# SDC_4.net
KiCad netlist of a schematic drawn in Altium Designer
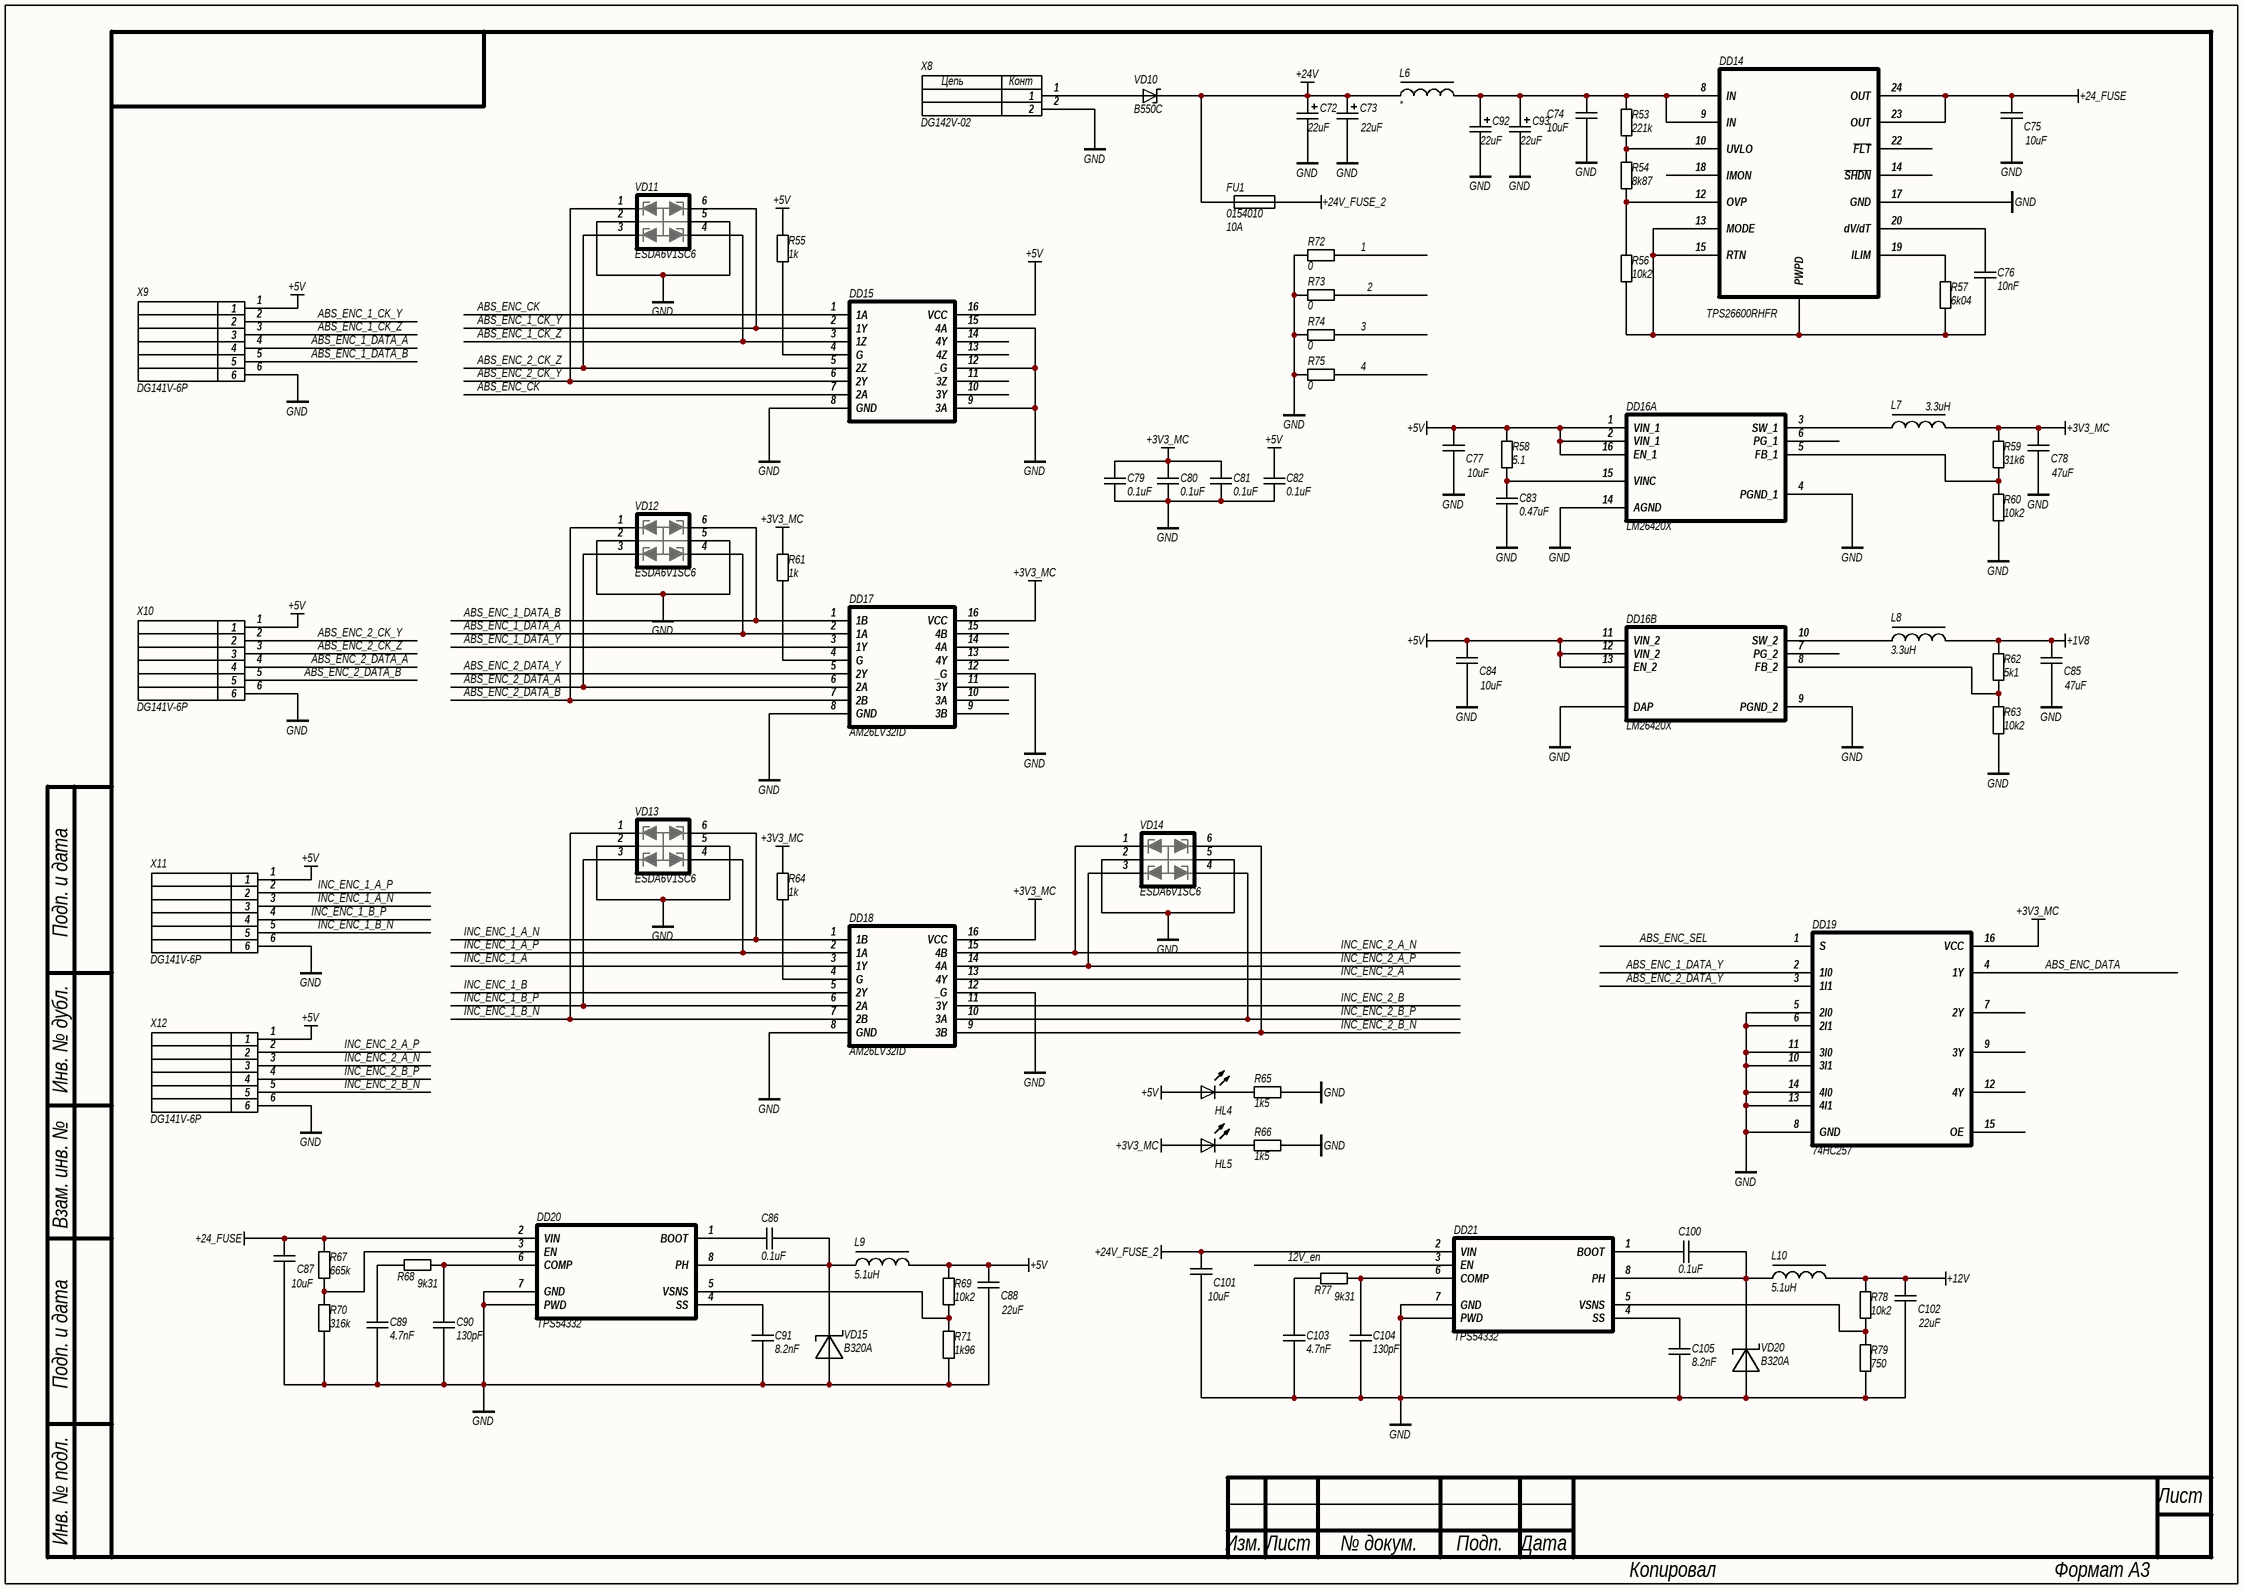
[diagram p0: SDC_4.SchDoc]

(export (version "E")
  (design (tool "Eeschema 10.0.6"))
  (components
    (comp (ref "C72")
      (value "22uF")
      (footprint "Cap_D")
      (description "Polarized Capacitor (Surface Mount)")
      (fields (field (name "VOLTAGE") "35V") (field (name "Comment") "caseD"))
      (libsource (lib "VKA") (part "Cap Pol_D"))
    )
    (comp (ref "C73")
      (value "22uF")
      (footprint "Cap_D")
      (description "Polarized Capacitor (Surface Mount)")
      (fields (field (name "VOLTAGE") "35V") (field (name "Comment") "caseD"))
      (libsource (lib "VKA") (part "Cap Pol_D"))
    )
    (comp (ref "C74")
      (value "10uF")
      (footprint "C1210")
      (description "SMD Capacitor")
      (fields (field (name "MANUFACTURER") "Murata") (field (name "TOLERANCE") "10%"))
      (libsource (lib "VKA") (part "CAP"))
    )
    (comp (ref "C75")
      (value "10uF")
      (footprint "C1210")
      (description "SMD Capacitor")
      (fields (field (name "MANUFACTURER") "Murata") (field (name "TOLERANCE") "10%"))
      (libsource (lib "VKA") (part "CAP"))
    )
    (comp (ref "C76")
      (value "10nF")
      (footprint "C0603")
      (description "SMD Capacitor")
      (fields (field (name "MANUFACTURER") "Murata") (field (name "TOLERANCE") "10%"))
      (libsource (lib "VKA") (part "CAP"))
    )
    (comp (ref "C77")
      (value "10uF")
      (footprint "C1210")
      (description "SMD Capacitor")
      (fields (field (name "MANUFACTURER") "Murata") (field (name "TOLERANCE") "10%"))
      (libsource (lib "VKA") (part "CAP"))
    )
    (comp (ref "C78")
      (value "47uF")
      (footprint "C1210")
      (description "SMD Capacitor")
      (fields (field (name "MANUFACTURER") "Murata") (field (name "TOLERANCE") "10%"))
      (libsource (lib "VKA") (part "CAP"))
    )
    (comp (ref "C79")
      (value "0.1uF")
      (footprint "C0603")
      (description "SMD Capacitor")
      (fields (field (name "MANUFACTURER") "Murata") (field (name "TOLERANCE") "10%"))
      (libsource (lib "VKA") (part "CAP"))
    )
    (comp (ref "C80")
      (value "0.1uF")
      (footprint "C0603")
      (description "SMD Capacitor")
      (fields (field (name "MANUFACTURER") "Murata") (field (name "TOLERANCE") "10%"))
      (libsource (lib "VKA") (part "CAP"))
    )
    (comp (ref "C81")
      (value "0.1uF")
      (footprint "C0603")
      (description "SMD Capacitor")
      (fields (field (name "MANUFACTURER") "Murata") (field (name "TOLERANCE") "10%"))
      (libsource (lib "VKA") (part "CAP"))
    )
    (comp (ref "C82")
      (value "0.1uF")
      (footprint "C0603")
      (description "SMD Capacitor")
      (fields (field (name "MANUFACTURER") "Murata") (field (name "TOLERANCE") "10%"))
      (libsource (lib "VKA") (part "CAP"))
    )
    (comp (ref "C83")
      (value "0.47uF")
      (footprint "C0603")
      (description "SMD Capacitor")
      (fields (field (name "MANUFACTURER") "Murata") (field (name "TOLERANCE") "10%"))
      (libsource (lib "VKA") (part "CAP"))
    )
    (comp (ref "C84")
      (value "10uF")
      (footprint "C1210")
      (description "SMD Capacitor")
      (fields (field (name "MANUFACTURER") "Murata") (field (name "TOLERANCE") "10%"))
      (libsource (lib "VKA") (part "CAP"))
    )
    (comp (ref "C85")
      (value "47uF")
      (footprint "C1210")
      (description "SMD Capacitor")
      (fields (field (name "MANUFACTURER") "Murata") (field (name "TOLERANCE") "10%"))
      (libsource (lib "VKA") (part "CAP"))
    )
    (comp (ref "C86")
      (value "0.1uF")
      (footprint "C0603")
      (description "SMD Capacitor")
      (fields (field (name "MANUFACTURER") "Murata") (field (name "TOLERANCE") "10%"))
      (libsource (lib "VKA") (part "CAP"))
    )
    (comp (ref "C87")
      (value "10uF")
      (footprint "C0805")
      (description "SMD Capacitor")
      (fields (field (name "MANUFACTURER") "Murata") (field (name "TOLERANCE") "10%"))
      (libsource (lib "VKA") (part "CAP"))
    )
    (comp (ref "C88")
      (value "22uF")
      (footprint "C1210")
      (description "SMD Capacitor")
      (fields (field (name "MANUFACTURER") "Murata") (field (name "TOLERANCE") "10%"))
      (libsource (lib "VKA") (part "CAP"))
    )
    (comp (ref "C89")
      (value "4.7nF")
      (footprint "C0603")
      (description "SMD Capacitor")
      (fields (field (name "MANUFACTURER") "Murata") (field (name "TOLERANCE") "10%"))
      (libsource (lib "VKA") (part "CAP"))
    )
    (comp (ref "C90")
      (value "130pF")
      (footprint "C0603")
      (description "SMD Capacitor")
      (fields (field (name "MANUFACTURER") "Murata") (field (name "TOLERANCE") "10%"))
      (libsource (lib "VKA") (part "CAP"))
    )
    (comp (ref "C91")
      (value "8.2nF")
      (footprint "C0603")
      (description "SMD Capacitor")
      (fields (field (name "MANUFACTURER") "Murata") (field (name "TOLERANCE") "10%"))
      (libsource (lib "VKA") (part "CAP"))
    )
    (comp (ref "C92")
      (value "22uF")
      (footprint "Cap_D")
      (description "Polarized Capacitor (Surface Mount)")
      (fields (field (name "VOLTAGE") "35V") (field (name "Comment") "caseD"))
      (libsource (lib "VKA") (part "Cap Pol_D"))
    )
    (comp (ref "C93")
      (value "22uF")
      (footprint "Cap_D")
      (description "Polarized Capacitor (Surface Mount)")
      (fields (field (name "VOLTAGE") "35V") (field (name "Comment") "caseD"))
      (libsource (lib "VKA") (part "Cap Pol_D"))
    )
    (comp (ref "C100")
      (value "0.1uF")
      (footprint "C0603")
      (description "SMD Capacitor")
      (fields (field (name "MANUFACTURER") "Murata") (field (name "TOLERANCE") "10%"))
      (libsource (lib "VKA") (part "CAP"))
    )
    (comp (ref "C101")
      (value "10uF")
      (footprint "C0805")
      (description "SMD Capacitor")
      (fields (field (name "MANUFACTURER") "Murata") (field (name "TOLERANCE") "10%"))
      (libsource (lib "VKA") (part "CAP"))
    )
    (comp (ref "C102")
      (value "22uF")
      (footprint "C1210")
      (description "SMD Capacitor")
      (fields (field (name "MANUFACTURER") "Murata") (field (name "TOLERANCE") "10%"))
      (libsource (lib "VKA") (part "CAP"))
    )
    (comp (ref "C103")
      (value "4.7nF")
      (footprint "C0603")
      (description "SMD Capacitor")
      (fields (field (name "MANUFACTURER") "Murata") (field (name "TOLERANCE") "10%"))
      (libsource (lib "VKA") (part "CAP"))
    )
    (comp (ref "C104")
      (value "130pF")
      (footprint "C0603")
      (description "SMD Capacitor")
      (fields (field (name "MANUFACTURER") "Murata") (field (name "TOLERANCE") "10%"))
      (libsource (lib "VKA") (part "CAP"))
    )
    (comp (ref "C105")
      (value "8.2nF")
      (footprint "C0603")
      (description "SMD Capacitor")
      (fields (field (name "MANUFACTURER") "Murata") (field (name "TOLERANCE") "10%"))
      (libsource (lib "VKA") (part "CAP"))
    )
    (comp (ref "DD14")
      (value "TPS26600RHFR")
      (footprint "VQFN24")
      (description "Industrial eFuse")
      (fields (field (name "VOLTAGE") "60V"))
      (libsource (lib "VKA") (part "TPS26600RHFR"))
    )
    (comp (ref "DD15")
      (value "AM26C31CD")
      (footprint "SO-16_N")
      (description "RS-422 transmitter")
      (libsource (lib "VKA") (part "AM26C31CD"))
    )
    (comp (ref "DD16") (value "LM26420X") (footprint "WQFN16") (libsource (lib "VKA") (part "LM26420X")))
    (comp (ref "DD17")
      (value "AM26LV32ID")
      (footprint "SO-16_N")
      (description "RS-422 receiver")
      (libsource (lib "VKA") (part "AM26LV32ID"))
    )
    (comp (ref "DD18")
      (value "AM26LV32ID")
      (footprint "SO-16_N")
      (description "RS-422 receiver")
      (libsource (lib "VKA") (part "AM26LV32ID"))
    )
    (comp (ref "DD19")
      (value "74HC257")
      (footprint "SO-16_N")
      (description "MUX")
      (libsource (lib "VKA") (part "74HC257"))
    )
    (comp (ref "DD20") (value "TPS54332") (footprint "DDA") (libsource (lib "VKA") (part "TPS54332")))
    (comp (ref "DD21") (value "TPS54332") (footprint "DDA") (libsource (lib "VKA") (part "TPS54332")))
    (comp (ref "FU1")
      (value "0154010")
      (footprint "omni_block_154")
      (description "omni fuse block")
      (fields (field (name "CURRENT") "10A"))
      (libsource (lib "DSP") (part "0154010"))
    )
    (comp (ref "HL4") (value "LED0603") (footprint "LED0603") (libsource (lib "VKA") (part "LED0603")))
    (comp (ref "HL5") (value "LED0603") (footprint "LED0603") (libsource (lib "VKA") (part "LED0603")))
    (comp (ref "L6")
      (value "XAL6060")
      (footprint "XAL6060")
      (description "chip inductor")
      (fields (field (name "ALTIUM_VALUE") "*"))
      (libsource (lib "VKA") (part "XAL6060"))
    )
    (comp (ref "L7")
      (value "3.3uH")
      (footprint "XAL4030")
      (description "chip inductor")
      (fields (field (name "Comment") "XAL4030"))
      (libsource (lib "VKA") (part "XAL4030"))
    )
    (comp (ref "L8")
      (value "3.3uH")
      (footprint "XAL4030")
      (description "chip inductor")
      (fields (field (name "Comment") "XAL4030"))
      (libsource (lib "VKA") (part "XAL4030"))
    )
    (comp (ref "L9")
      (value "5.1uH")
      (footprint "XAL5050")
      (description "chip inductor")
      (fields (field (name "Comment") "XAL5050"))
      (libsource (lib "VKA") (part "XAL5050"))
    )
    (comp (ref "L10")
      (value "5.1uH")
      (footprint "XAL5050")
      (description "chip inductor")
      (fields (field (name "Comment") "XAL5050"))
      (libsource (lib "VKA") (part "XAL5050"))
    )
    (comp (ref "R53")
      (value "221k")
      (footprint "R0603")
      (description "SMD Resistor")
      (fields (field (name "POWER") "0.062 Wt") (field (name "TOLERANCE") "5%"))
      (libsource (lib "VKA") (part "RES"))
    )
    (comp (ref "R54")
      (value "8k87")
      (footprint "R0603")
      (description "SMD Resistor")
      (fields (field (name "POWER") "0.062 Wt") (field (name "TOLERANCE") "5%"))
      (libsource (lib "VKA") (part "RES"))
    )
    (comp (ref "R55")
      (value "1k")
      (footprint "R0603")
      (description "SMD Resistor")
      (fields (field (name "POWER") "0.062 Wt") (field (name "TOLERANCE") "5%"))
      (libsource (lib "VKA") (part "RES"))
    )
    (comp (ref "R56")
      (value "10k2")
      (footprint "R0603")
      (description "SMD Resistor")
      (fields (field (name "POWER") "0.062 Wt") (field (name "TOLERANCE") "5%"))
      (libsource (lib "VKA") (part "RES"))
    )
    (comp (ref "R57")
      (value "6k04")
      (footprint "R0603")
      (description "SMD Resistor")
      (fields (field (name "POWER") "0.062 Wt") (field (name "TOLERANCE") "5%"))
      (libsource (lib "VKA") (part "RES"))
    )
    (comp (ref "R58")
      (value "5.1")
      (footprint "R0603")
      (description "SMD Resistor")
      (fields (field (name "POWER") "0.062 Wt") (field (name "TOLERANCE") "5%"))
      (libsource (lib "VKA") (part "RES"))
    )
    (comp (ref "R59")
      (value "31k6")
      (footprint "R0603")
      (description "SMD Resistor")
      (fields (field (name "POWER") "0.062 Wt") (field (name "TOLERANCE") "5%"))
      (libsource (lib "VKA") (part "RES"))
    )
    (comp (ref "R60")
      (value "10k2")
      (footprint "R0603")
      (description "SMD Resistor")
      (fields (field (name "POWER") "0.062 Wt") (field (name "TOLERANCE") "5%"))
      (libsource (lib "VKA") (part "RES"))
    )
    (comp (ref "R61")
      (value "1k")
      (footprint "R0603")
      (description "SMD Resistor")
      (fields (field (name "POWER") "0.062 Wt") (field (name "TOLERANCE") "5%"))
      (libsource (lib "VKA") (part "RES"))
    )
    (comp (ref "R62")
      (value "5k1")
      (footprint "R0603")
      (description "SMD Resistor")
      (fields (field (name "POWER") "0.062 Wt") (field (name "TOLERANCE") "5%"))
      (libsource (lib "VKA") (part "RES"))
    )
    (comp (ref "R63")
      (value "10k2")
      (footprint "R0603")
      (description "SMD Resistor")
      (fields (field (name "POWER") "0.062 Wt") (field (name "TOLERANCE") "5%"))
      (libsource (lib "VKA") (part "RES"))
    )
    (comp (ref "R64")
      (value "1k")
      (footprint "R0603")
      (description "SMD Resistor")
      (fields (field (name "POWER") "0.062 Wt") (field (name "TOLERANCE") "5%"))
      (libsource (lib "VKA") (part "RES"))
    )
    (comp (ref "R65")
      (value "1k5")
      (footprint "R0603")
      (description "SMD Resistor")
      (fields (field (name "POWER") "0.062 Wt") (field (name "TOLERANCE") "5%"))
      (libsource (lib "") (part "RES_1"))
    )
    (comp (ref "R66")
      (value "1k5")
      (footprint "R0603")
      (description "SMD Resistor")
      (fields (field (name "POWER") "0.062 Wt") (field (name "TOLERANCE") "5%"))
      (libsource (lib "") (part "RES_1"))
    )
    (comp (ref "R67")
      (value "665k")
      (footprint "R0603")
      (description "SMD Resistor")
      (fields (field (name "POWER") "0.062 Wt") (field (name "TOLERANCE") "5%"))
      (libsource (lib "VKA") (part "RES"))
    )
    (comp (ref "R68")
      (value "9k31")
      (footprint "R0603")
      (description "SMD Resistor")
      (fields (field (name "POWER") "0.062 Wt") (field (name "TOLERANCE") "5%"))
      (libsource (lib "") (part "RES_1"))
    )
    (comp (ref "R69")
      (value "10k2")
      (footprint "R0603")
      (description "SMD Resistor")
      (fields (field (name "POWER") "0.062 Wt") (field (name "TOLERANCE") "5%"))
      (libsource (lib "VKA") (part "RES"))
    )
    (comp (ref "R70")
      (value "316k")
      (footprint "R0603")
      (description "SMD Resistor")
      (fields (field (name "POWER") "0.062 Wt") (field (name "TOLERANCE") "5%"))
      (libsource (lib "VKA") (part "RES"))
    )
    (comp (ref "R71")
      (value "1k96")
      (footprint "R0603")
      (description "SMD Resistor")
      (fields (field (name "POWER") "0.062 Wt") (field (name "TOLERANCE") "5%"))
      (libsource (lib "VKA") (part "RES"))
    )
    (comp (ref "R72")
      (value "0")
      (footprint "R0603")
      (description "SMD Resistor")
      (fields (field (name "POWER") "0.062 Wt") (field (name "TOLERANCE") "5%"))
      (libsource (lib "") (part "RES_1"))
    )
    (comp (ref "R73")
      (value "0")
      (footprint "R0603")
      (description "SMD Resistor")
      (fields (field (name "POWER") "0.062 Wt") (field (name "TOLERANCE") "5%"))
      (libsource (lib "") (part "RES_1"))
    )
    (comp (ref "R74")
      (value "0")
      (footprint "R0603")
      (description "SMD Resistor")
      (fields (field (name "POWER") "0.062 Wt") (field (name "TOLERANCE") "5%"))
      (libsource (lib "") (part "RES_1"))
    )
    (comp (ref "R75")
      (value "0")
      (footprint "R0603")
      (description "SMD Resistor")
      (fields (field (name "POWER") "0.062 Wt") (field (name "TOLERANCE") "5%"))
      (libsource (lib "") (part "RES_1"))
    )
    (comp (ref "R77")
      (value "9k31")
      (footprint "R0603")
      (description "SMD Resistor")
      (fields (field (name "POWER") "0.062 Wt") (field (name "TOLERANCE") "5%"))
      (libsource (lib "") (part "RES_1"))
    )
    (comp (ref "R78")
      (value "10k2")
      (footprint "R0603")
      (description "SMD Resistor")
      (fields (field (name "POWER") "0.062 Wt") (field (name "TOLERANCE") "5%"))
      (libsource (lib "VKA") (part "RES"))
    )
    (comp (ref "R79")
      (value "750")
      (footprint "R0603")
      (description "SMD Resistor")
      (fields (field (name "POWER") "0.062 Wt") (field (name "TOLERANCE") "5%"))
      (libsource (lib "VKA") (part "RES"))
    )
    (comp (ref "VD10")
      (value "B550C")
      (footprint "SMC-DO214")
      (description "DIODE, SCHOTTKY, 5A, 50V, SMC")
      (libsource (lib "VKA") (part "B550C"))
    )
    (comp (ref "VD11")
      (value "ESDA6V1SC6")
      (footprint "SOT23-6")
      (description "4-line ESD protection")
      (libsource (lib "VKA") (part "ESDA6V1SC6"))
    )
    (comp (ref "VD12")
      (value "ESDA6V1SC6")
      (footprint "SOT23-6")
      (description "4-line ESD protection")
      (libsource (lib "VKA") (part "ESDA6V1SC6"))
    )
    (comp (ref "VD13")
      (value "ESDA6V1SC6")
      (footprint "SOT23-6")
      (description "4-line ESD protection")
      (libsource (lib "VKA") (part "ESDA6V1SC6"))
    )
    (comp (ref "VD14")
      (value "ESDA6V1SC6")
      (footprint "SOT23-6")
      (description "4-line ESD protection")
      (libsource (lib "VKA") (part "ESDA6V1SC6"))
    )
    (comp (ref "VD15")
      (value "B320A")
      (footprint "SMA-DO214")
      (description "Shottky diode")
      (libsource (lib "VKA") (part "B320A"))
    )
    (comp (ref "VD20")
      (value "B320A")
      (footprint "SMA-DO214")
      (description "Shottky diode")
      (libsource (lib "VKA") (part "B320A"))
    )
    (comp (ref "X8") (value "DG142V-02") (footprint "DG142V-02") (libsource (lib "VKA") (part "DG142V-02")))
    (comp (ref "X9")
      (value "DG141V-6P")
      (footprint "DG141V-06P")
      (description "wire connector")
      (libsource (lib "VKA") (part "DG141V-6P"))
    )
    (comp (ref "X10")
      (value "DG141V-6P")
      (footprint "DG141V-06P")
      (description "wire connector")
      (libsource (lib "VKA") (part "DG141V-6P"))
    )
    (comp (ref "X11")
      (value "DG141V-6P")
      (footprint "DG141V-06P")
      (description "wire connector")
      (libsource (lib "VKA") (part "DG141V-6P"))
    )
    (comp (ref "X12")
      (value "DG141V-6P")
      (footprint "DG141V-06P")
      (description "wire connector")
      (libsource (lib "VKA") (part "DG141V-6P"))
    )
  )
  (nets
    (net (code "1") (name "+1V8") (class "Default")
      (node (ref "C85") (pin "2") (pinfunction "2_2") (pintype "passive"))
      (node (ref "L8") (pin "2") (pinfunction "2_2") (pintype "passive"))
      (node (ref "R62") (pin "2") (pinfunction "2_2") (pintype "passive"))
    )
    (net (code "2") (name "+3V3_MC") (class "Default")
      (node (ref "C78") (pin "2") (pinfunction "2_2") (pintype "passive"))
      (node (ref "C79") (pin "2") (pinfunction "2_2") (pintype "passive"))
      (node (ref "C80") (pin "2") (pinfunction "2_2") (pintype "passive"))
      (node (ref "C81") (pin "2") (pinfunction "2_2") (pintype "passive"))
      (node (ref "DD17") (pin "16") (pinfunction "VCC_16") (pintype "passive"))
      (node (ref "DD18") (pin "16") (pinfunction "VCC_16") (pintype "passive"))
      (node (ref "DD19") (pin "16") (pinfunction "VCC_16") (pintype "passive"))
      (node (ref "HL5") (pin "1") (pinfunction "A_1") (pintype "passive"))
      (node (ref "L7") (pin "2") (pinfunction "2_2") (pintype "passive"))
      (node (ref "R59") (pin "2") (pinfunction "2_2") (pintype "passive"))
      (node (ref "R61") (pin "2") (pinfunction "2_2") (pintype "passive"))
      (node (ref "R64") (pin "2") (pinfunction "2_2") (pintype "passive"))
    )
    (net (code "3") (name "+5V") (class "Default")
      (node (ref "C77") (pin "2") (pinfunction "2_2") (pintype "passive"))
      (node (ref "C82") (pin "2") (pinfunction "2_2") (pintype "passive"))
      (node (ref "C84") (pin "2") (pinfunction "2_2") (pintype "passive"))
      (node (ref "C88") (pin "2") (pinfunction "2_2") (pintype "passive"))
      (node (ref "DD15") (pin "16") (pinfunction "VCC_16") (pintype "passive"))
      (node (ref "DD16") (pin "1") (pinfunction "VIN_1_1") (pintype "passive"))
      (node (ref "DD16") (pin "11") (pinfunction "VIN_2_11") (pintype "passive"))
      (node (ref "DD16") (pin "12") (pinfunction "VIN_2_12") (pintype "passive"))
      (node (ref "DD16") (pin "13") (pinfunction "EN_2_13") (pintype "passive"))
      (node (ref "DD16") (pin "16") (pinfunction "EN_1_16") (pintype "passive"))
      (node (ref "DD16") (pin "2") (pinfunction "VIN_1_2") (pintype "passive"))
      (node (ref "HL4") (pin "1") (pinfunction "A_1") (pintype "passive"))
      (node (ref "L9") (pin "2") (pinfunction "2_2") (pintype "passive"))
      (node (ref "R55") (pin "2") (pinfunction "2_2") (pintype "passive"))
      (node (ref "R58") (pin "2") (pinfunction "2_2") (pintype "passive"))
      (node (ref "R69") (pin "2") (pinfunction "2_2") (pintype "passive"))
      (node (ref "X10") (pin "1") (pinfunction "1_1") (pintype "passive"))
      (node (ref "X11") (pin "1") (pinfunction "1_1") (pintype "passive"))
      (node (ref "X12") (pin "1") (pinfunction "1_1") (pintype "passive"))
      (node (ref "X9") (pin "1") (pinfunction "1_1") (pintype "passive"))
    )
    (net (code "4") (name "+12V") (class "Default")
      (node (ref "C102") (pin "2") (pinfunction "2_2") (pintype "passive"))
      (node (ref "L10") (pin "2") (pinfunction "2_2") (pintype "passive"))
      (node (ref "R78") (pin "2") (pinfunction "2_2") (pintype "passive"))
    )
    (net (code "5") (name "+24V") (class "Default")
      (node (ref "C72") (pin "1") (pinfunction "1_1") (pintype "passive"))
      (node (ref "C73") (pin "1") (pinfunction "1_1") (pintype "passive"))
      (node (ref "FU1") (pin "1") (pinfunction "1_1") (pintype "passive"))
      (node (ref "L6") (pin "1") (pinfunction "1_1") (pintype "passive"))
      (node (ref "VD10") (pin "2") (pinfunction "K_2") (pintype "passive"))
    )
    (net (code "6") (name "+24V_FUSE_2") (class "Default")
      (node (ref "C101") (pin "2") (pinfunction "2_2") (pintype "passive"))
      (node (ref "DD21") (pin "2") (pinfunction "VIN_2") (pintype "passive"))
      (node (ref "FU1") (pin "2") (pinfunction "2_2") (pintype "passive"))
    )
    (net (code "7") (name "+24_FUSE") (class "Default")
      (node (ref "C75") (pin "2") (pinfunction "2_2") (pintype "passive"))
      (node (ref "C87") (pin "2") (pinfunction "2_2") (pintype "passive"))
      (node (ref "DD14") (pin "23") (pinfunction "OUT_23") (pintype "passive"))
      (node (ref "DD14") (pin "24") (pinfunction "OUT_24") (pintype "passive"))
      (node (ref "DD20") (pin "2") (pinfunction "VIN_2") (pintype "passive"))
      (node (ref "R67") (pin "2") (pinfunction "2_2") (pintype "passive"))
    )
    (net (code "8") (name "/1") (class "Default")
      (node (ref "R72") (pin "1") (pinfunction "1_1") (pintype "passive"))
    )
    (net (code "9") (name "/2") (class "Default")
      (node (ref "R73") (pin "1") (pinfunction "1_1") (pintype "passive"))
    )
    (net (code "10") (name "/3") (class "Default")
      (node (ref "R74") (pin "1") (pinfunction "1_1") (pintype "passive"))
    )
    (net (code "11") (name "/4") (class "Default")
      (node (ref "R75") (pin "1") (pinfunction "1_1") (pintype "passive"))
    )
    (net (code "12") (name "/12V_en") (class "Default")
      (node (ref "DD21") (pin "3") (pinfunction "EN_3") (pintype "passive"))
    )
    (net (code "13") (name "/ABS_ENC_1_CK_Y") (class "Default")
      (node (ref "DD15") (pin "2") (pinfunction "1Y_2") (pintype "passive"))
      (node (ref "VD11") (pin "6") (pinfunction "6_6") (pintype "passive"))
      (node (ref "X9") (pin "2") (pinfunction "2_2") (pintype "passive"))
    )
    (net (code "14") (name "/ABS_ENC_1_CK_Z") (class "Default")
      (node (ref "DD15") (pin "3") (pinfunction "1Z_3") (pintype "passive"))
      (node (ref "VD11") (pin "4") (pinfunction "4_4") (pintype "passive"))
      (node (ref "X9") (pin "3") (pinfunction "3_3") (pintype "passive"))
    )
    (net (code "15") (name "/ABS_ENC_1_DATA_A") (class "Default")
      (node (ref "DD17") (pin "2") (pinfunction "1A_2") (pintype "passive"))
      (node (ref "VD12") (pin "4") (pinfunction "4_4") (pintype "passive"))
      (node (ref "X9") (pin "4") (pinfunction "4_4") (pintype "passive"))
    )
    (net (code "16") (name "/ABS_ENC_1_DATA_B") (class "Default")
      (node (ref "DD17") (pin "1") (pinfunction "1B_1") (pintype "passive"))
      (node (ref "VD12") (pin "6") (pinfunction "6_6") (pintype "passive"))
      (node (ref "X9") (pin "5") (pinfunction "5_5") (pintype "passive"))
    )
    (net (code "17") (name "/ABS_ENC_1_DATA_Y") (class "Default")
      (node (ref "DD17") (pin "3") (pinfunction "1Y_3") (pintype "passive"))
      (node (ref "DD19") (pin "2") (pinfunction "1I0_2") (pintype "passive"))
    )
    (net (code "18") (name "/ABS_ENC_2_CK_Y") (class "Default")
      (node (ref "DD15") (pin "6") (pinfunction "2Y_6") (pintype "passive"))
      (node (ref "VD11") (pin "1") (pinfunction "1_1") (pintype "passive"))
      (node (ref "X10") (pin "2") (pinfunction "2_2") (pintype "passive"))
    )
    (net (code "19") (name "/ABS_ENC_2_CK_Z") (class "Default")
      (node (ref "DD15") (pin "5") (pinfunction "2Z_5") (pintype "passive"))
      (node (ref "VD11") (pin "3") (pinfunction "3_3") (pintype "passive"))
      (node (ref "X10") (pin "3") (pinfunction "3_3") (pintype "passive"))
    )
    (net (code "20") (name "/ABS_ENC_2_DATA_A") (class "Default")
      (node (ref "DD17") (pin "6") (pinfunction "2A_6") (pintype "passive"))
      (node (ref "VD12") (pin "3") (pinfunction "3_3") (pintype "passive"))
      (node (ref "X10") (pin "4") (pinfunction "4_4") (pintype "passive"))
    )
    (net (code "21") (name "/ABS_ENC_2_DATA_B") (class "Default")
      (node (ref "DD17") (pin "7") (pinfunction "2B_7") (pintype "passive"))
      (node (ref "VD12") (pin "1") (pinfunction "1_1") (pintype "passive"))
      (node (ref "X10") (pin "5") (pinfunction "5_5") (pintype "passive"))
    )
    (net (code "22") (name "/ABS_ENC_2_DATA_Y") (class "Default")
      (node (ref "DD17") (pin "5") (pinfunction "2Y_5") (pintype "passive"))
      (node (ref "DD19") (pin "3") (pinfunction "1I1_3") (pintype "passive"))
    )
    (net (code "23") (name "/ABS_ENC_CK") (class "Default")
      (node (ref "DD15") (pin "1") (pinfunction "1A_1") (pintype "passive"))
      (node (ref "DD15") (pin "7") (pinfunction "2A_7") (pintype "passive"))
    )
    (net (code "24") (name "/ABS_ENC_DATA") (class "Default")
      (node (ref "DD19") (pin "4") (pinfunction "1Y_4") (pintype "passive"))
    )
    (net (code "25") (name "/ABS_ENC_SEL") (class "Default")
      (node (ref "DD19") (pin "1") (pinfunction "S_1") (pintype "passive"))
    )
    (net (code "26") (name "/INC_ENC_1_A") (class "Default")
      (node (ref "DD18") (pin "3") (pinfunction "1Y_3") (pintype "passive"))
    )
    (net (code "27") (name "/INC_ENC_1_A_N") (class "Default")
      (node (ref "DD18") (pin "1") (pinfunction "1B_1") (pintype "passive"))
      (node (ref "VD13") (pin "6") (pinfunction "6_6") (pintype "passive"))
      (node (ref "X11") (pin "3") (pinfunction "3_3") (pintype "passive"))
    )
    (net (code "28") (name "/INC_ENC_1_A_P") (class "Default")
      (node (ref "DD18") (pin "2") (pinfunction "1A_2") (pintype "passive"))
      (node (ref "VD13") (pin "4") (pinfunction "4_4") (pintype "passive"))
      (node (ref "X11") (pin "2") (pinfunction "2_2") (pintype "passive"))
    )
    (net (code "29") (name "/INC_ENC_1_B") (class "Default")
      (node (ref "DD18") (pin "5") (pinfunction "2Y_5") (pintype "passive"))
    )
    (net (code "30") (name "/INC_ENC_1_B_N") (class "Default")
      (node (ref "DD18") (pin "7") (pinfunction "2B_7") (pintype "passive"))
      (node (ref "VD13") (pin "1") (pinfunction "1_1") (pintype "passive"))
      (node (ref "X11") (pin "5") (pinfunction "5_5") (pintype "passive"))
    )
    (net (code "31") (name "/INC_ENC_1_B_P") (class "Default")
      (node (ref "DD18") (pin "6") (pinfunction "2A_6") (pintype "passive"))
      (node (ref "VD13") (pin "3") (pinfunction "3_3") (pintype "passive"))
      (node (ref "X11") (pin "4") (pinfunction "4_4") (pintype "passive"))
    )
    (net (code "32") (name "/INC_ENC_2_A") (class "Default")
      (node (ref "DD18") (pin "13") (pinfunction "4Y_13") (pintype "passive"))
    )
    (net (code "33") (name "/INC_ENC_2_A_N") (class "Default")
      (node (ref "DD18") (pin "15") (pinfunction "4B_15") (pintype "passive"))
      (node (ref "VD14") (pin "1") (pinfunction "1_1") (pintype "passive"))
      (node (ref "X12") (pin "3") (pinfunction "3_3") (pintype "passive"))
    )
    (net (code "34") (name "/INC_ENC_2_A_P") (class "Default")
      (node (ref "DD18") (pin "14") (pinfunction "4A_14") (pintype "passive"))
      (node (ref "VD14") (pin "3") (pinfunction "3_3") (pintype "passive"))
      (node (ref "X12") (pin "2") (pinfunction "2_2") (pintype "passive"))
    )
    (net (code "35") (name "/INC_ENC_2_B") (class "Default")
      (node (ref "DD18") (pin "11") (pinfunction "3Y_11") (pintype "passive"))
    )
    (net (code "36") (name "/INC_ENC_2_B_N") (class "Default")
      (node (ref "DD18") (pin "9") (pinfunction "3B_9") (pintype "passive"))
      (node (ref "VD14") (pin "6") (pinfunction "6_6") (pintype "passive"))
      (node (ref "X12") (pin "5") (pinfunction "5_5") (pintype "passive"))
    )
    (net (code "37") (name "/INC_ENC_2_B_P") (class "Default")
      (node (ref "DD18") (pin "10") (pinfunction "3A_10") (pintype "passive"))
      (node (ref "VD14") (pin "4") (pinfunction "4_4") (pintype "passive"))
      (node (ref "X12") (pin "4") (pinfunction "4_4") (pintype "passive"))
    )
    (net (code "38") (name "GND") (class "Default")
      (node (ref "C101") (pin "1") (pinfunction "1_1") (pintype "passive"))
      (node (ref "C102") (pin "1") (pinfunction "1_1") (pintype "passive"))
      (node (ref "C103") (pin "1") (pinfunction "1_1") (pintype "passive"))
      (node (ref "C104") (pin "1") (pinfunction "1_1") (pintype "passive"))
      (node (ref "C105") (pin "1") (pinfunction "1_1") (pintype "passive"))
      (node (ref "C72") (pin "2") (pinfunction "2_2") (pintype "passive"))
      (node (ref "C73") (pin "2") (pinfunction "2_2") (pintype "passive"))
      (node (ref "C74") (pin "1") (pinfunction "1_1") (pintype "passive"))
      (node (ref "C75") (pin "1") (pinfunction "1_1") (pintype "passive"))
      (node (ref "C77") (pin "1") (pinfunction "1_1") (pintype "passive"))
      (node (ref "C78") (pin "1") (pinfunction "1_1") (pintype "passive"))
      (node (ref "C79") (pin "1") (pinfunction "1_1") (pintype "passive"))
      (node (ref "C80") (pin "1") (pinfunction "1_1") (pintype "passive"))
      (node (ref "C81") (pin "1") (pinfunction "1_1") (pintype "passive"))
      (node (ref "C82") (pin "1") (pinfunction "1_1") (pintype "passive"))
      (node (ref "C83") (pin "1") (pinfunction "1_1") (pintype "passive"))
      (node (ref "C84") (pin "1") (pinfunction "1_1") (pintype "passive"))
      (node (ref "C85") (pin "1") (pinfunction "1_1") (pintype "passive"))
      (node (ref "C87") (pin "1") (pinfunction "1_1") (pintype "passive"))
      (node (ref "C88") (pin "1") (pinfunction "1_1") (pintype "passive"))
      (node (ref "C89") (pin "1") (pinfunction "1_1") (pintype "passive"))
      (node (ref "C90") (pin "1") (pinfunction "1_1") (pintype "passive"))
      (node (ref "C91") (pin "1") (pinfunction "1_1") (pintype "passive"))
      (node (ref "C92") (pin "2") (pinfunction "2_2") (pintype "passive"))
      (node (ref "C93") (pin "2") (pinfunction "2_2") (pintype "passive"))
      (node (ref "DD14") (pin "17") (pinfunction "GND_17") (pintype "passive"))
      (node (ref "DD15") (pin "12") (pinfunction "_G_12") (pintype "passive"))
      (node (ref "DD15") (pin "15") (pinfunction "4A_15") (pintype "passive"))
      (node (ref "DD15") (pin "8") (pinfunction "GND_8") (pintype "passive"))
      (node (ref "DD15") (pin "9") (pinfunction "3A_9") (pintype "passive"))
      (node (ref "DD16") (pin "14") (pinfunction "AGND_14") (pintype "passive"))
      (node (ref "DD16") (pin "17") (pinfunction "DAP_17") (pintype "passive"))
      (node (ref "DD16") (pin "4") (pinfunction "PGND_1_4") (pintype "passive"))
      (node (ref "DD16") (pin "9") (pinfunction "PGND_2_9") (pintype "passive"))
      (node (ref "DD17") (pin "12") (pinfunction "_G_12") (pintype "passive"))
      (node (ref "DD17") (pin "8") (pinfunction "GND_8") (pintype "passive"))
      (node (ref "DD18") (pin "12") (pinfunction "_G_12") (pintype "passive"))
      (node (ref "DD18") (pin "8") (pinfunction "GND_8") (pintype "passive"))
      (node (ref "DD19") (pin "10") (pinfunction "3I1_10") (pintype "passive"))
      (node (ref "DD19") (pin "11") (pinfunction "3I0_11") (pintype "passive"))
      (node (ref "DD19") (pin "13") (pinfunction "4I1_13") (pintype "passive"))
      (node (ref "DD19") (pin "14") (pinfunction "4I0_14") (pintype "passive"))
      (node (ref "DD19") (pin "5") (pinfunction "2I0_5") (pintype "passive"))
      (node (ref "DD19") (pin "6") (pinfunction "2I1_6") (pintype "passive"))
      (node (ref "DD19") (pin "8") (pinfunction "GND_8") (pintype "passive"))
      (node (ref "DD20") (pin "7") (pinfunction "GND_7") (pintype "passive"))
      (node (ref "DD20") (pin "9") (pinfunction "PWD_9") (pintype "passive"))
      (node (ref "DD21") (pin "7") (pinfunction "GND_7") (pintype "passive"))
      (node (ref "DD21") (pin "9") (pinfunction "PWD_9") (pintype "passive"))
      (node (ref "R60") (pin "1") (pinfunction "1_1") (pintype "passive"))
      (node (ref "R63") (pin "1") (pinfunction "1_1") (pintype "passive"))
      (node (ref "R65") (pin "1") (pinfunction "1_1") (pintype "passive"))
      (node (ref "R66") (pin "1") (pinfunction "1_1") (pintype "passive"))
      (node (ref "R70") (pin "1") (pinfunction "1_1") (pintype "passive"))
      (node (ref "R71") (pin "1") (pinfunction "1_1") (pintype "passive"))
      (node (ref "R72") (pin "2") (pinfunction "2_2") (pintype "passive"))
      (node (ref "R73") (pin "2") (pinfunction "2_2") (pintype "passive"))
      (node (ref "R74") (pin "2") (pinfunction "2_2") (pintype "passive"))
      (node (ref "R75") (pin "2") (pinfunction "2_2") (pintype "passive"))
      (node (ref "R79") (pin "1") (pinfunction "1_1") (pintype "passive"))
      (node (ref "VD11") (pin "2") (pinfunction "2_2") (pintype "passive"))
      (node (ref "VD11") (pin "5") (pinfunction "5_5") (pintype "passive"))
      (node (ref "VD12") (pin "2") (pinfunction "2_2") (pintype "passive"))
      (node (ref "VD12") (pin "5") (pinfunction "5_5") (pintype "passive"))
      (node (ref "VD13") (pin "2") (pinfunction "2_2") (pintype "passive"))
      (node (ref "VD13") (pin "5") (pinfunction "5_5") (pintype "passive"))
      (node (ref "VD14") (pin "2") (pinfunction "2_2") (pintype "passive"))
      (node (ref "VD14") (pin "5") (pinfunction "5_5") (pintype "passive"))
      (node (ref "VD15") (pin "1") (pinfunction "A_1") (pintype "passive"))
      (node (ref "VD20") (pin "1") (pinfunction "A_1") (pintype "passive"))
      (node (ref "X10") (pin "6") (pinfunction "6_6") (pintype "passive"))
      (node (ref "X11") (pin "6") (pinfunction "6_6") (pintype "passive"))
      (node (ref "X12") (pin "6") (pinfunction "6_6") (pintype "passive"))
      (node (ref "X8") (pin "2") (pinfunction "2_2") (pintype "passive"))
      (node (ref "X9") (pin "6") (pinfunction "6_6") (pintype "passive"))
    )
    (net (code "39") (name "Net-(C74-Pad2)") (class "Default")
      (node (ref "C74") (pin "2") (pinfunction "2_2") (pintype "passive"))
      (node (ref "C92") (pin "1") (pinfunction "1_1") (pintype "passive"))
      (node (ref "C93") (pin "1") (pinfunction "1_1") (pintype "passive"))
      (node (ref "DD14") (pin "8") (pinfunction "IN_8") (pintype "passive"))
      (node (ref "DD14") (pin "9") (pinfunction "IN_9") (pintype "passive"))
      (node (ref "L6") (pin "2") (pinfunction "2_2") (pintype "passive"))
      (node (ref "R53") (pin "2") (pinfunction "2_2") (pintype "passive"))
    )
    (net (code "40") (name "Net-(C89-Pad2)") (class "Default")
      (node (ref "C89") (pin "2") (pinfunction "2_2") (pintype "passive"))
      (node (ref "R68") (pin "2") (pinfunction "2_2") (pintype "passive"))
    )
    (net (code "41") (name "Net-(C103-Pad2)") (class "Default")
      (node (ref "C103") (pin "2") (pinfunction "2_2") (pintype "passive"))
      (node (ref "R77") (pin "2") (pinfunction "2_2") (pintype "passive"))
    )
    (net (code "42") (name "Net-(DD14-ILIM)") (class "Default")
      (node (ref "DD14") (pin "19") (pinfunction "ILIM_19") (pintype "passive"))
      (node (ref "R57") (pin "2") (pinfunction "2_2") (pintype "passive"))
    )
    (net (code "43") (name "Net-(DD14-MODE)") (class "Default")
      (node (ref "C76") (pin "1") (pinfunction "1_1") (pintype "passive"))
      (node (ref "DD14") (pin "13") (pinfunction "MODE_13") (pintype "passive"))
      (node (ref "DD14") (pin "15") (pinfunction "RTN_15") (pintype "passive"))
      (node (ref "DD14") (pin "25") (pinfunction "PWPD_25") (pintype "passive"))
      (node (ref "R56") (pin "1") (pinfunction "1_1") (pintype "passive"))
      (node (ref "R57") (pin "1") (pinfunction "1_1") (pintype "passive"))
    )
    (net (code "44") (name "Net-(DD14-OVP)") (class "Default")
      (node (ref "DD14") (pin "12") (pinfunction "OVP_12") (pintype "passive"))
      (node (ref "R54") (pin "1") (pinfunction "1_1") (pintype "passive"))
      (node (ref "R56") (pin "2") (pinfunction "2_2") (pintype "passive"))
    )
    (net (code "45") (name "Net-(DD14-UVLO)") (class "Default")
      (node (ref "DD14") (pin "10") (pinfunction "UVLO_10") (pintype "passive"))
      (node (ref "R53") (pin "1") (pinfunction "1_1") (pintype "passive"))
      (node (ref "R54") (pin "2") (pinfunction "2_2") (pintype "passive"))
    )
    (net (code "46") (name "Net-(DD14-dV{slash}dT)") (class "Default")
      (node (ref "C76") (pin "2") (pinfunction "2_2") (pintype "passive"))
      (node (ref "DD14") (pin "20") (pinfunction "dV/dT_20") (pintype "passive"))
    )
    (net (code "47") (name "Net-(DD15-G)") (class "Default")
      (node (ref "DD15") (pin "4") (pinfunction "G_4") (pintype "passive"))
      (node (ref "R55") (pin "1") (pinfunction "1_1") (pintype "passive"))
    )
    (net (code "48") (name "Net-(DD16A-FB_1)") (class "Default")
      (node (ref "DD16") (pin "5") (pinfunction "FB_1_5") (pintype "passive"))
      (node (ref "R59") (pin "1") (pinfunction "1_1") (pintype "passive"))
      (node (ref "R60") (pin "2") (pinfunction "2_2") (pintype "passive"))
    )
    (net (code "49") (name "Net-(DD16A-SW_1)") (class "Default")
      (node (ref "DD16") (pin "3") (pinfunction "SW_1_3") (pintype "passive"))
      (node (ref "L7") (pin "1") (pinfunction "1_1") (pintype "passive"))
    )
    (net (code "50") (name "Net-(DD16A-VINC)") (class "Default")
      (node (ref "C83") (pin "2") (pinfunction "2_2") (pintype "passive"))
      (node (ref "DD16") (pin "15") (pinfunction "VINC_15") (pintype "passive"))
      (node (ref "R58") (pin "1") (pinfunction "1_1") (pintype "passive"))
    )
    (net (code "51") (name "Net-(DD16B-FB_2)") (class "Default")
      (node (ref "DD16") (pin "8") (pinfunction "FB_2_8") (pintype "passive"))
      (node (ref "R62") (pin "1") (pinfunction "1_1") (pintype "passive"))
      (node (ref "R63") (pin "2") (pinfunction "2_2") (pintype "passive"))
    )
    (net (code "52") (name "Net-(DD16B-SW_2)") (class "Default")
      (node (ref "DD16") (pin "10") (pinfunction "SW_2_10") (pintype "passive"))
      (node (ref "L8") (pin "1") (pinfunction "1_1") (pintype "passive"))
    )
    (net (code "53") (name "Net-(DD17-G)") (class "Default")
      (node (ref "DD17") (pin "4") (pinfunction "G_4") (pintype "passive"))
      (node (ref "R61") (pin "1") (pinfunction "1_1") (pintype "passive"))
    )
    (net (code "54") (name "Net-(DD18-G)") (class "Default")
      (node (ref "DD18") (pin "4") (pinfunction "G_4") (pintype "passive"))
      (node (ref "R64") (pin "1") (pinfunction "1_1") (pintype "passive"))
    )
    (net (code "55") (name "Net-(DD20-BOOT)") (class "Default")
      (node (ref "C86") (pin "2") (pinfunction "2_2") (pintype "passive"))
      (node (ref "DD20") (pin "1") (pinfunction "BOOT_1") (pintype "passive"))
    )
    (net (code "56") (name "Net-(DD20-COMP)") (class "Default")
      (node (ref "C90") (pin "2") (pinfunction "2_2") (pintype "passive"))
      (node (ref "DD20") (pin "6") (pinfunction "COMP_6") (pintype "passive"))
      (node (ref "R68") (pin "1") (pinfunction "1_1") (pintype "passive"))
    )
    (net (code "57") (name "Net-(DD20-EN)") (class "Default")
      (node (ref "DD20") (pin "3") (pinfunction "EN_3") (pintype "passive"))
      (node (ref "R67") (pin "1") (pinfunction "1_1") (pintype "passive"))
      (node (ref "R70") (pin "2") (pinfunction "2_2") (pintype "passive"))
    )
    (net (code "58") (name "Net-(DD20-PH)") (class "Default")
      (node (ref "C86") (pin "1") (pinfunction "1_1") (pintype "passive"))
      (node (ref "DD20") (pin "8") (pinfunction "PH_8") (pintype "passive"))
      (node (ref "L9") (pin "1") (pinfunction "1_1") (pintype "passive"))
      (node (ref "VD15") (pin "2") (pinfunction "K_2") (pintype "passive"))
    )
    (net (code "59") (name "Net-(DD20-SS)") (class "Default")
      (node (ref "C91") (pin "2") (pinfunction "2_2") (pintype "passive"))
      (node (ref "DD20") (pin "4") (pinfunction "SS_4") (pintype "passive"))
    )
    (net (code "60") (name "Net-(DD20-VSNS)") (class "Default")
      (node (ref "DD20") (pin "5") (pinfunction "VSNS_5") (pintype "passive"))
      (node (ref "R69") (pin "1") (pinfunction "1_1") (pintype "passive"))
      (node (ref "R71") (pin "2") (pinfunction "2_2") (pintype "passive"))
    )
    (net (code "61") (name "Net-(DD21-BOOT)") (class "Default")
      (node (ref "C100") (pin "2") (pinfunction "2_2") (pintype "passive"))
      (node (ref "DD21") (pin "1") (pinfunction "BOOT_1") (pintype "passive"))
    )
    (net (code "62") (name "Net-(DD21-COMP)") (class "Default")
      (node (ref "C104") (pin "2") (pinfunction "2_2") (pintype "passive"))
      (node (ref "DD21") (pin "6") (pinfunction "COMP_6") (pintype "passive"))
      (node (ref "R77") (pin "1") (pinfunction "1_1") (pintype "passive"))
    )
    (net (code "63") (name "Net-(DD21-PH)") (class "Default")
      (node (ref "C100") (pin "1") (pinfunction "1_1") (pintype "passive"))
      (node (ref "DD21") (pin "8") (pinfunction "PH_8") (pintype "passive"))
      (node (ref "L10") (pin "1") (pinfunction "1_1") (pintype "passive"))
      (node (ref "VD20") (pin "2") (pinfunction "K_2") (pintype "passive"))
    )
    (net (code "64") (name "Net-(DD21-SS)") (class "Default")
      (node (ref "C105") (pin "2") (pinfunction "2_2") (pintype "passive"))
      (node (ref "DD21") (pin "4") (pinfunction "SS_4") (pintype "passive"))
    )
    (net (code "65") (name "Net-(DD21-VSNS)") (class "Default")
      (node (ref "DD21") (pin "5") (pinfunction "VSNS_5") (pintype "passive"))
      (node (ref "R78") (pin "1") (pinfunction "1_1") (pintype "passive"))
      (node (ref "R79") (pin "2") (pinfunction "2_2") (pintype "passive"))
    )
    (net (code "66") (name "Net-(HL4-K)") (class "Default")
      (node (ref "HL4") (pin "2") (pinfunction "K_2") (pintype "passive"))
      (node (ref "R65") (pin "2") (pinfunction "2_2") (pintype "passive"))
    )
    (net (code "67") (name "Net-(HL5-K)") (class "Default")
      (node (ref "HL5") (pin "2") (pinfunction "K_2") (pintype "passive"))
      (node (ref "R66") (pin "2") (pinfunction "2_2") (pintype "passive"))
    )
    (net (code "68") (name "Net-(VD10-A)") (class "Default")
      (node (ref "VD10") (pin "1") (pinfunction "A_1") (pintype "passive"))
      (node (ref "X8") (pin "1") (pinfunction "1_1") (pintype "passive"))
    )
    (net (code "69") (name "unconnected-(DD14-IMON-Pad18)") (class "Default")
      (node (ref "DD14") (pin "18") (pinfunction "IMON_18") (pintype "passive"))
    )
    (net (code "70") (name "unconnected-(DD14-~{FLT}-Pad22)") (class "Default")
      (node (ref "DD14") (pin "22") (pinfunction "~{FLT}_22") (pintype "passive"))
    )
    (net (code "71") (name "unconnected-(DD14-~{SHDN}-Pad14)") (class "Default")
      (node (ref "DD14") (pin "14") (pinfunction "~{SHDN}_14") (pintype "passive"))
    )
    (net (code "72") (name "unconnected-(DD15-3Y-Pad10)") (class "Default")
      (node (ref "DD15") (pin "10") (pinfunction "3Y_10") (pintype "passive"))
    )
    (net (code "73") (name "unconnected-(DD15-3Z-Pad11)") (class "Default")
      (node (ref "DD15") (pin "11") (pinfunction "3Z_11") (pintype "passive"))
    )
    (net (code "74") (name "unconnected-(DD15-4Y-Pad14)") (class "Default")
      (node (ref "DD15") (pin "14") (pinfunction "4Y_14") (pintype "passive"))
    )
    (net (code "75") (name "unconnected-(DD15-4Z-Pad13)") (class "Default")
      (node (ref "DD15") (pin "13") (pinfunction "4Z_13") (pintype "passive"))
    )
    (net (code "76") (name "unconnected-(DD16A-PG_1-Pad6)") (class "Default")
      (node (ref "DD16") (pin "6") (pinfunction "PG_1_6") (pintype "passive"))
    )
    (net (code "77") (name "unconnected-(DD16B-PG_2-Pad7)") (class "Default")
      (node (ref "DD16") (pin "7") (pinfunction "PG_2_7") (pintype "passive"))
    )
    (net (code "78") (name "unconnected-(DD17-3A-Pad10)") (class "Default")
      (node (ref "DD17") (pin "10") (pinfunction "3A_10") (pintype "passive"))
    )
    (net (code "79") (name "unconnected-(DD17-3B-Pad9)") (class "Default")
      (node (ref "DD17") (pin "9") (pinfunction "3B_9") (pintype "passive"))
    )
    (net (code "80") (name "unconnected-(DD17-3Y-Pad11)") (class "Default")
      (node (ref "DD17") (pin "11") (pinfunction "3Y_11") (pintype "passive"))
    )
    (net (code "81") (name "unconnected-(DD17-4A-Pad14)") (class "Default")
      (node (ref "DD17") (pin "14") (pinfunction "4A_14") (pintype "passive"))
    )
    (net (code "82") (name "unconnected-(DD17-4B-Pad15)") (class "Default")
      (node (ref "DD17") (pin "15") (pinfunction "4B_15") (pintype "passive"))
    )
    (net (code "83") (name "unconnected-(DD17-4Y-Pad13)") (class "Default")
      (node (ref "DD17") (pin "13") (pinfunction "4Y_13") (pintype "passive"))
    )
    (net (code "84") (name "unconnected-(DD19-2Y-Pad7)") (class "Default")
      (node (ref "DD19") (pin "7") (pinfunction "2Y_7") (pintype "passive"))
    )
    (net (code "85") (name "unconnected-(DD19-3Y-Pad9)") (class "Default")
      (node (ref "DD19") (pin "9") (pinfunction "3Y_9") (pintype "passive"))
    )
    (net (code "86") (name "unconnected-(DD19-4Y-Pad12)") (class "Default")
      (node (ref "DD19") (pin "12") (pinfunction "4Y_12") (pintype "passive"))
    )
    (net (code "87") (name "unconnected-(DD19-OE-Pad15)") (class "Default")
      (node (ref "DD19") (pin "15") (pinfunction "OE_15") (pintype "passive"))
    )
  )
)
